# janus.net
KiCad netlist of a schematic drawn in EAGLE
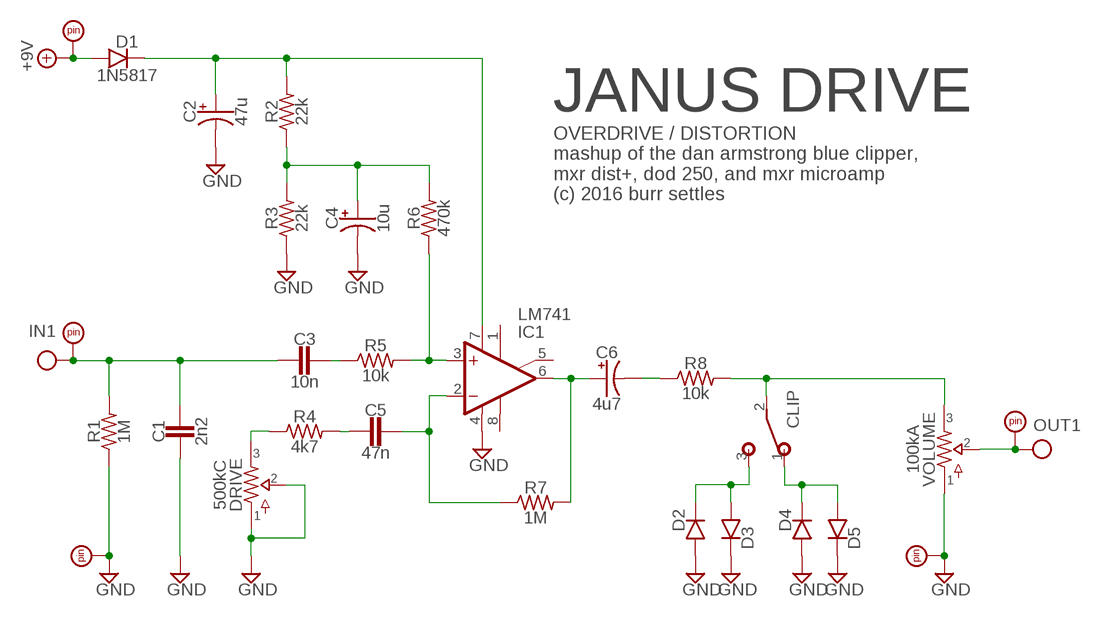
[diagram p0: schematic, sheet 1]

(export (version "E")
  (design (tool "Eeschema 10.0.6"))
  (components
    (comp (ref "C1")
      (value "2n2")
      (footprint "eagle-import:BOX_SMALL")
      (libsource (lib "eagle-import") (part "CER/FILMBOX.1"))
    )
    (comp (ref "C2")
      (value "47u")
      (footprint "eagle-import:050_020_1")
      (libsource (lib "eagle-import") (part "0501"))
    )
    (comp (ref "C3")
      (value "10n")
      (footprint "eagle-import:BOX_SMALL")
      (libsource (lib "eagle-import") (part "CER/FILMBOX.1"))
    )
    (comp (ref "C4")
      (value "10u")
      (footprint "eagle-import:050_020_1")
      (libsource (lib "eagle-import") (part "0501"))
    )
    (comp (ref "C5")
      (value "47n")
      (footprint "eagle-import:BOX_SMALL")
      (libsource (lib "eagle-import") (part "CER/FILMBOX.1"))
    )
    (comp (ref "C6")
      (value "4u7")
      (footprint "eagle-import:050_020_1")
      (libsource (lib "eagle-import") (part "0501"))
    )
    (comp (ref "CLIP")
      (value "SPDTPADS")
      (footprint "eagle-import:SPDT")
      (libsource (lib "eagle-import") (part "SPDTPADS"))
    )
    (comp (ref "D1")
      (value "1N5817")
      (footprint "eagle-import:DO41-2")
      (libsource (lib "eagle-import") (part "DO41.2"))
    )
    (comp (ref "D2")
      (value "DO35.2")
      (footprint "eagle-import:DO35-2")
      (libsource (lib "eagle-import") (part "DO35.2"))
    )
    (comp (ref "D3")
      (value "DO35.2")
      (footprint "eagle-import:DO35-2")
      (libsource (lib "eagle-import") (part "DO35.2"))
    )
    (comp (ref "D4")
      (value "DO35.3")
      (footprint "eagle-import:DO35-3")
      (libsource (lib "eagle-import") (part "DO35.3"))
    )
    (comp (ref "D5")
      (value "DO35.3")
      (footprint "eagle-import:DO35-3")
      (libsource (lib "eagle-import") (part "DO35.3"))
    )
    (comp (ref "DRIVE")
      (value "500kC")
      (footprint "eagle-import:PADS_SMALL")
      (libsource (lib "eagle-import") (part "POTSSMALL_PADS"))
    )
    (comp (ref "IC1")
      (value "LM741")
      (footprint "eagle-import:DIL08")
      (libsource (lib "eagle-import") (part "SINGLETH"))
    )
    (comp (ref "PAD1")
      (value "PADSQR")
      (footprint "eagle-import:SQUARE")
      (libsource (lib "eagle-import") (part "PADSQR"))
    )
    (comp (ref "PAD2")
      (value "PADSQR")
      (footprint "eagle-import:SQUARE")
      (libsource (lib "eagle-import") (part "PADSQR"))
    )
    (comp (ref "PAD3")
      (value "PADRND")
      (footprint "eagle-import:ROUND")
      (libsource (lib "eagle-import") (part "PADRND"))
    )
    (comp (ref "PAD4")
      (value "PADRND")
      (footprint "eagle-import:ROUND")
      (libsource (lib "eagle-import") (part "PADRND"))
    )
    (comp (ref "PAD5")
      (value "PADSQR")
      (footprint "eagle-import:SQUARE")
      (libsource (lib "eagle-import") (part "PADSQR"))
    )
    (comp (ref "R1")
      (value "1M")
      (footprint "eagle-import:R0207_3")
      (libsource (lib "eagle-import") (part "R_.3B"))
    )
    (comp (ref "R2")
      (value "22k")
      (footprint "eagle-import:R0207_3")
      (libsource (lib "eagle-import") (part "R_.3B"))
    )
    (comp (ref "R3")
      (value "22k")
      (footprint "eagle-import:R0207_3")
      (libsource (lib "eagle-import") (part "R_.3B"))
    )
    (comp (ref "R4")
      (value "4k7")
      (footprint "eagle-import:R0207_3")
      (libsource (lib "eagle-import") (part "R_.3B"))
    )
    (comp (ref "R5")
      (value "10k")
      (footprint "eagle-import:R0207_3")
      (libsource (lib "eagle-import") (part "R_.3B"))
    )
    (comp (ref "R6")
      (value "470k")
      (footprint "eagle-import:R0207_3")
      (libsource (lib "eagle-import") (part "R_.3B"))
    )
    (comp (ref "R7")
      (value "1M")
      (footprint "eagle-import:R0207_3")
      (libsource (lib "eagle-import") (part "R_.3B"))
    )
    (comp (ref "R8")
      (value "10k")
      (footprint "eagle-import:R0207_3")
      (libsource (lib "eagle-import") (part "R_.3B"))
    )
    (comp (ref "VOLUME")
      (value "100kA")
      (footprint "eagle-import:PADS_SMALL")
      (libsource (lib "eagle-import") (part "POTSSMALL_PADS"))
    )
  )
  (nets
    (net (code "1") (name "+9V") (class "Default")
      (node (ref "D1") (pin "A") (pinfunction "A_A") (pintype "passive"))
      (node (ref "PAD1") (pin "1") (pinfunction "P$1_1") (pintype "bidirectional"))
    )
    (net (code "2") (name "GND") (class "Default")
      (node (ref "C1") (pin "1") (pinfunction "1_1") (pintype "passive"))
      (node (ref "C2") (pin "-") (pinfunction "-_-") (pintype "passive"))
      (node (ref "C4") (pin "-") (pinfunction "-_-") (pintype "passive"))
      (node (ref "D2") (pin "A") (pinfunction "A_A") (pintype "passive"))
      (node (ref "D3") (pin "C") (pinfunction "C_C") (pintype "passive"))
      (node (ref "D4") (pin "A") (pinfunction "A_A") (pintype "passive"))
      (node (ref "D5") (pin "C") (pinfunction "C_C") (pintype "passive"))
      (node (ref "DRIVE") (pin "1") (pinfunction "1_1") (pintype "passive"))
      (node (ref "DRIVE") (pin "2") (pinfunction "2_2") (pintype "passive"))
      (node (ref "IC1") (pin "4") (pinfunction "V-_4") (pintype "power_in"))
      (node (ref "PAD3") (pin "1") (pinfunction "P$1_1") (pintype "bidirectional"))
      (node (ref "PAD4") (pin "1") (pinfunction "P$1_1") (pintype "bidirectional"))
      (node (ref "R1") (pin "1") (pinfunction "1_1") (pintype "passive"))
      (node (ref "R3") (pin "1") (pinfunction "1_1") (pintype "passive"))
      (node (ref "VOLUME") (pin "1") (pinfunction "1_1") (pintype "passive"))
    )
    (net (code "3") (name "IN") (class "Default")
      (node (ref "C1") (pin "2") (pinfunction "2_2") (pintype "passive"))
      (node (ref "C3") (pin "2") (pinfunction "2_2") (pintype "passive"))
      (node (ref "PAD2") (pin "1") (pinfunction "P$1_1") (pintype "bidirectional"))
      (node (ref "R1") (pin "2") (pinfunction "2_2") (pintype "passive"))
    )
    (net (code "4") (name "Net-(C3-Pad1)") (class "Default")
      (node (ref "C3") (pin "1") (pinfunction "1_1") (pintype "passive"))
      (node (ref "R5") (pin "1") (pinfunction "1_1") (pintype "passive"))
    )
    (net (code "5") (name "Net-(C4-Pad+)") (class "Default")
      (node (ref "C4") (pin "+") (pinfunction "+_+") (pintype "passive"))
      (node (ref "R2") (pin "1") (pinfunction "1_1") (pintype "passive"))
      (node (ref "R3") (pin "2") (pinfunction "2_2") (pintype "passive"))
      (node (ref "R6") (pin "2") (pinfunction "2_2") (pintype "passive"))
    )
    (net (code "6") (name "Net-(C5-Pad2)") (class "Default")
      (node (ref "C5") (pin "2") (pinfunction "2_2") (pintype "passive"))
      (node (ref "R4") (pin "2") (pinfunction "2_2") (pintype "passive"))
    )
    (net (code "7") (name "Net-(C6-Pad-)") (class "Default")
      (node (ref "C6") (pin "-") (pinfunction "-_-") (pintype "passive"))
      (node (ref "R8") (pin "1") (pinfunction "1_1") (pintype "passive"))
    )
    (net (code "8") (name "Net-(CLIP-O)") (class "Default")
      (node (ref "CLIP") (pin "1") (pinfunction "O_1") (pintype "passive"))
      (node (ref "D4") (pin "C") (pinfunction "C_C") (pintype "passive"))
      (node (ref "D5") (pin "A") (pinfunction "A_A") (pintype "passive"))
    )
    (net (code "9") (name "Net-(CLIP-P)") (class "Default")
      (node (ref "CLIP") (pin "2") (pinfunction "P_2") (pintype "passive"))
      (node (ref "R8") (pin "2") (pinfunction "2_2") (pintype "passive"))
      (node (ref "VOLUME") (pin "3") (pinfunction "3_3") (pintype "passive"))
    )
    (net (code "10") (name "Net-(CLIP-S)") (class "Default")
      (node (ref "CLIP") (pin "3") (pinfunction "S_3") (pintype "passive"))
      (node (ref "D2") (pin "C") (pinfunction "C_C") (pintype "passive"))
      (node (ref "D3") (pin "A") (pinfunction "A_A") (pintype "passive"))
    )
    (net (code "11") (name "Net-(DRIVE-Pad3)") (class "Default")
      (node (ref "DRIVE") (pin "3") (pinfunction "3_3") (pintype "passive"))
      (node (ref "R4") (pin "1") (pinfunction "1_1") (pintype "passive"))
    )
    (net (code "12") (name "Net-(IC1-+IN)") (class "Default")
      (node (ref "IC1") (pin "3") (pinfunction "+IN_3") (pintype "input"))
      (node (ref "R5") (pin "2") (pinfunction "2_2") (pintype "passive"))
      (node (ref "R6") (pin "1") (pinfunction "1_1") (pintype "passive"))
    )
    (net (code "13") (name "Net-(IC1--IN)") (class "Default")
      (node (ref "C5") (pin "1") (pinfunction "1_1") (pintype "passive"))
      (node (ref "IC1") (pin "2") (pinfunction "-IN_2") (pintype "input"))
      (node (ref "R7") (pin "1") (pinfunction "1_1") (pintype "passive"))
    )
    (net (code "14") (name "Net-(IC1-OUT)") (class "Default")
      (node (ref "C6") (pin "+") (pinfunction "+_+") (pintype "passive"))
      (node (ref "IC1") (pin "6") (pinfunction "OUT_6") (pintype "output"))
      (node (ref "R7") (pin "2") (pinfunction "2_2") (pintype "passive"))
    )
    (net (code "15") (name "Net-(IC1-V+)") (class "Default")
      (node (ref "C2") (pin "+") (pinfunction "+_+") (pintype "passive"))
      (node (ref "D1") (pin "C") (pinfunction "C_C") (pintype "passive"))
      (node (ref "IC1") (pin "7") (pinfunction "V+_7") (pintype "power_in"))
      (node (ref "R2") (pin "2") (pinfunction "2_2") (pintype "passive"))
    )
    (net (code "16") (name "OUT") (class "Default")
      (node (ref "PAD5") (pin "1") (pinfunction "P$1_1") (pintype "bidirectional"))
      (node (ref "VOLUME") (pin "2") (pinfunction "2_2") (pintype "passive"))
    )
    (net (code "17") (name "unconnected-(IC1-ON1-Pad1)") (class "Default")
      (node (ref "IC1") (pin "1") (pinfunction "ON1_1") (pintype "passive"))
    )
    (net (code "18") (name "unconnected-(IC1-ON2-Pad5)") (class "Default")
      (node (ref "IC1") (pin "5") (pinfunction "ON2_5") (pintype "passive"))
    )
    (net (code "19") (name "unconnected-(IC1-OPT-Pad8)") (class "Default")
      (node (ref "IC1") (pin "8") (pinfunction "OPT_8") (pintype "passive"))
    )
  )
)
